# FET_bord.net
KiCad netlist of a schematic drawn in EAGLE
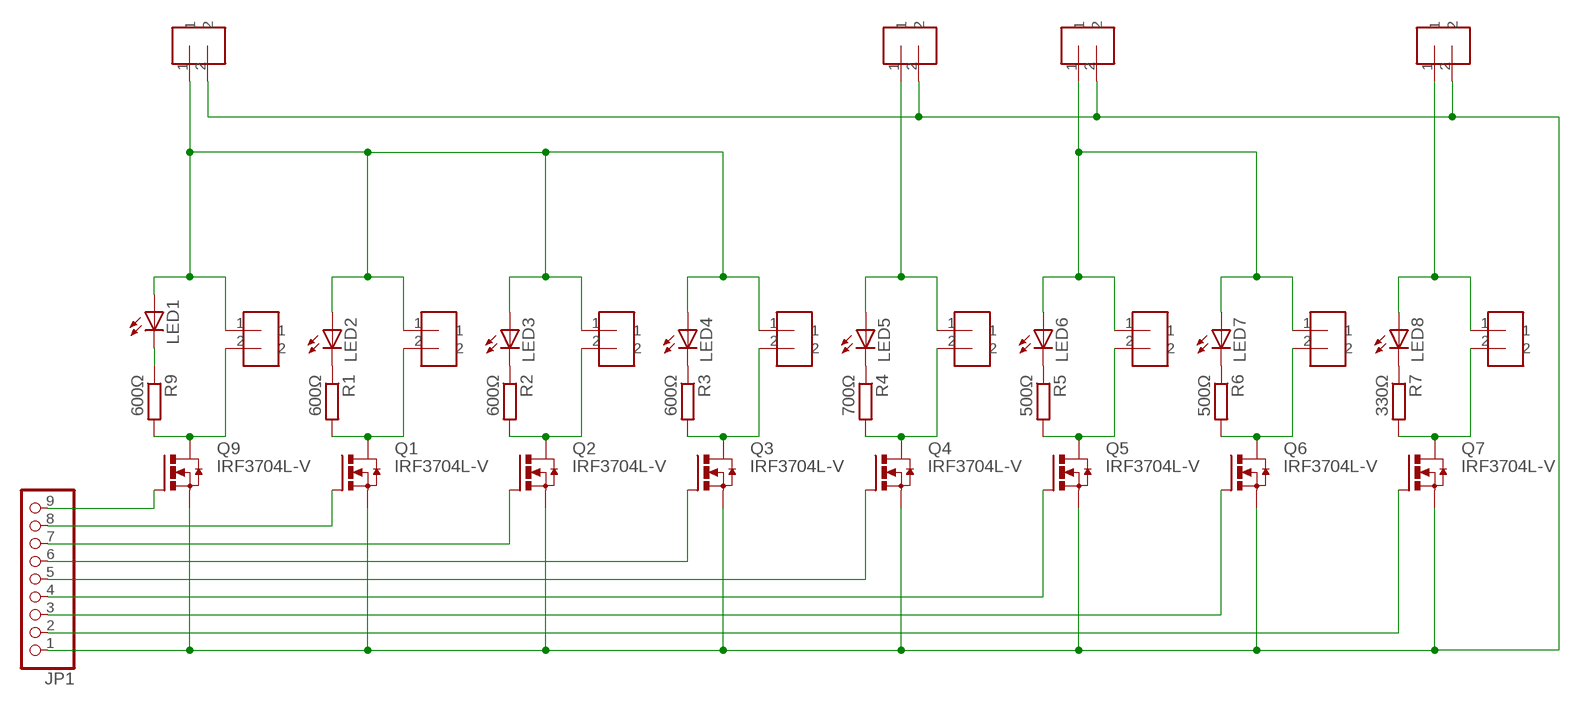
[diagram p0: schematic, sheet 1]

(export (version "E")
  (design (tool "Eeschema 10.0.6"))
  (components
    (comp (ref "3.3V")
      (value "TERMINAL_BLOCK_5.08MM")
      (footprint "eagle-import:TERMINAL_BLOCK_5.8MM")
      (libsource (lib "eagle-import") (part "TERMINAL_BLOCK_5.08MM"))
    )
    (comp (ref "5V")
      (value "TERMINAL_BLOCK_5.08MM")
      (footprint "eagle-import:TERMINAL_BLOCK_5.8MM")
      (libsource (lib "eagle-import") (part "TERMINAL_BLOCK_5.08MM"))
    )
    (comp (ref "7V")
      (value "TERMINAL_BLOCK_5.08MM")
      (footprint "eagle-import:TERMINAL_BLOCK_5.8MM")
      (libsource (lib "eagle-import") (part "TERMINAL_BLOCK_5.08MM"))
    )
    (comp (ref "12V")
      (value "TERMINAL_BLOCK_5.08MM")
      (footprint "eagle-import:TERMINAL_BLOCK_5.8MM")
      (libsource (lib "eagle-import") (part "TERMINAL_BLOCK_5.08MM"))
    )
    (comp (ref "JP1")
      (value "PINHD-1X9")
      (footprint "eagle-import:1X09")
      (libsource (lib "eagle-import") (part "PINHD-1X9"))
    )
    (comp (ref "LED1")
      (value "LED3MM")
      (footprint "eagle-import:LED3MM")
      (libsource (lib "eagle-import") (part "LED3MM"))
    )
    (comp (ref "LED2")
      (value "LED3MM")
      (footprint "eagle-import:LED3MM")
      (libsource (lib "eagle-import") (part "LED3MM"))
    )
    (comp (ref "LED3")
      (value "LED3MM")
      (footprint "eagle-import:LED3MM")
      (libsource (lib "eagle-import") (part "LED3MM"))
    )
    (comp (ref "LED4")
      (value "LED3MM")
      (footprint "eagle-import:LED3MM")
      (libsource (lib "eagle-import") (part "LED3MM"))
    )
    (comp (ref "LED5")
      (value "LED3MM")
      (footprint "eagle-import:LED3MM")
      (libsource (lib "eagle-import") (part "LED3MM"))
    )
    (comp (ref "LED6")
      (value "LED3MM")
      (footprint "eagle-import:LED3MM")
      (libsource (lib "eagle-import") (part "LED3MM"))
    )
    (comp (ref "LED7")
      (value "LED3MM")
      (footprint "eagle-import:LED3MM")
      (libsource (lib "eagle-import") (part "LED3MM"))
    )
    (comp (ref "LED8")
      (value "LED3MM")
      (footprint "eagle-import:LED3MM")
      (libsource (lib "eagle-import") (part "LED3MM"))
    )
    (comp (ref "Q1")
      (value "IRF3704L-V")
      (footprint "eagle-import:TO262-V")
      (libsource (lib "eagle-import") (part "IRF3704L-V"))
    )
    (comp (ref "Q2")
      (value "IRF3704L-V")
      (footprint "eagle-import:TO262-V")
      (libsource (lib "eagle-import") (part "IRF3704L-V"))
    )
    (comp (ref "Q3")
      (value "IRF3704L-V")
      (footprint "eagle-import:TO262-V")
      (libsource (lib "eagle-import") (part "IRF3704L-V"))
    )
    (comp (ref "Q4")
      (value "IRF3704L-V")
      (footprint "eagle-import:TO262-V")
      (libsource (lib "eagle-import") (part "IRF3704L-V"))
    )
    (comp (ref "Q5")
      (value "IRF3704L-V")
      (footprint "eagle-import:TO262-V")
      (libsource (lib "eagle-import") (part "IRF3704L-V"))
    )
    (comp (ref "Q6")
      (value "IRF3704L-V")
      (footprint "eagle-import:TO262-V")
      (libsource (lib "eagle-import") (part "IRF3704L-V"))
    )
    (comp (ref "Q7")
      (value "IRF3704L-V")
      (footprint "eagle-import:TO262-V")
      (libsource (lib "eagle-import") (part "IRF3704L-V"))
    )
    (comp (ref "Q9")
      (value "IRF3704L-V")
      (footprint "eagle-import:TO262-V")
      (libsource (lib "eagle-import") (part "IRF3704L-V"))
    )
    (comp (ref "R1")
      (value "600Ω")
      (footprint "eagle-import:0207_15")
      (libsource (lib "eagle-import") (part "R-EU_0207/15"))
    )
    (comp (ref "R2")
      (value "600Ω")
      (footprint "eagle-import:0207_15")
      (libsource (lib "eagle-import") (part "R-EU_0207/15"))
    )
    (comp (ref "R3")
      (value "600Ω")
      (footprint "eagle-import:0207_15")
      (libsource (lib "eagle-import") (part "R-EU_0207/15"))
    )
    (comp (ref "R4")
      (value "700Ω")
      (footprint "eagle-import:0207_15")
      (libsource (lib "eagle-import") (part "R-EU_0207/15"))
    )
    (comp (ref "R5")
      (value "500Ω")
      (footprint "eagle-import:0207_15")
      (libsource (lib "eagle-import") (part "R-EU_0207/15"))
    )
    (comp (ref "R6")
      (value "500Ω")
      (footprint "eagle-import:0207_15")
      (libsource (lib "eagle-import") (part "R-EU_0207/15"))
    )
    (comp (ref "R7")
      (value "330Ω")
      (footprint "eagle-import:0207_15")
      (libsource (lib "eagle-import") (part "R-EU_0207/15"))
    )
    (comp (ref "R9")
      (value "600Ω")
      (footprint "eagle-import:0207_15")
      (libsource (lib "eagle-import") (part "R-EU_0207/15"))
    )
    (comp (ref "U$1")
      (value "TERMINAL_BLOCK_5.08MM")
      (footprint "eagle-import:TERMINAL_BLOCK_5.8MM")
      (libsource (lib "eagle-import") (part "TERMINAL_BLOCK_5.08MM"))
    )
    (comp (ref "U$2")
      (value "TERMINAL_BLOCK_5.08MM")
      (footprint "eagle-import:TERMINAL_BLOCK_5.8MM")
      (libsource (lib "eagle-import") (part "TERMINAL_BLOCK_5.08MM"))
    )
    (comp (ref "U$3")
      (value "TERMINAL_BLOCK_5.08MM")
      (footprint "eagle-import:TERMINAL_BLOCK_5.8MM")
      (libsource (lib "eagle-import") (part "TERMINAL_BLOCK_5.08MM"))
    )
    (comp (ref "U$4")
      (value "TERMINAL_BLOCK_5.08MM")
      (footprint "eagle-import:TERMINAL_BLOCK_5.8MM")
      (libsource (lib "eagle-import") (part "TERMINAL_BLOCK_5.08MM"))
    )
    (comp (ref "U$5")
      (value "TERMINAL_BLOCK_5.08MM")
      (footprint "eagle-import:TERMINAL_BLOCK_5.8MM")
      (libsource (lib "eagle-import") (part "TERMINAL_BLOCK_5.08MM"))
    )
    (comp (ref "U$6")
      (value "TERMINAL_BLOCK_5.08MM")
      (footprint "eagle-import:TERMINAL_BLOCK_5.8MM")
      (libsource (lib "eagle-import") (part "TERMINAL_BLOCK_5.08MM"))
    )
    (comp (ref "U$7")
      (value "TERMINAL_BLOCK_5.08MM")
      (footprint "eagle-import:TERMINAL_BLOCK_5.8MM")
      (libsource (lib "eagle-import") (part "TERMINAL_BLOCK_5.08MM"))
    )
    (comp (ref "U$8")
      (value "TERMINAL_BLOCK_5.08MM")
      (footprint "eagle-import:TERMINAL_BLOCK_5.8MM")
      (libsource (lib "eagle-import") (part "TERMINAL_BLOCK_5.08MM"))
    )
  )
  (nets
    (net (code "1") (name "Net-(3.3V-Pad1)") (class "Default")
      (node (ref "3.3V") (pin "1") (pinfunction "1_1") (pintype "bidirectional"))
      (node (ref "LED8") (pin "A") (pinfunction "A_A") (pintype "passive"))
      (node (ref "U$8") (pin "1") (pinfunction "1_1") (pintype "bidirectional"))
    )
    (net (code "2") (name "Net-(5V-Pad1)") (class "Default")
      (node (ref "5V") (pin "1") (pinfunction "1_1") (pintype "bidirectional"))
      (node (ref "LED6") (pin "A") (pinfunction "A_A") (pintype "passive"))
      (node (ref "LED7") (pin "A") (pinfunction "A_A") (pintype "passive"))
      (node (ref "U$6") (pin "1") (pinfunction "1_1") (pintype "bidirectional"))
      (node (ref "U$7") (pin "1") (pinfunction "1_1") (pintype "bidirectional"))
    )
    (net (code "3") (name "Net-(7V-Pad1)") (class "Default")
      (node (ref "7V") (pin "1") (pinfunction "1_1") (pintype "bidirectional"))
      (node (ref "LED5") (pin "A") (pinfunction "A_A") (pintype "passive"))
      (node (ref "U$5") (pin "1") (pinfunction "1_1") (pintype "bidirectional"))
    )
    (net (code "4") (name "Net-(12V-Pad1)") (class "Default")
      (node (ref "12V") (pin "1") (pinfunction "1_1") (pintype "bidirectional"))
      (node (ref "LED1") (pin "A") (pinfunction "A_A") (pintype "passive"))
      (node (ref "LED2") (pin "A") (pinfunction "A_A") (pintype "passive"))
      (node (ref "LED3") (pin "A") (pinfunction "A_A") (pintype "passive"))
      (node (ref "LED4") (pin "A") (pinfunction "A_A") (pintype "passive"))
      (node (ref "U$1") (pin "1") (pinfunction "1_1") (pintype "bidirectional"))
      (node (ref "U$2") (pin "1") (pinfunction "1_1") (pintype "bidirectional"))
      (node (ref "U$3") (pin "1") (pinfunction "1_1") (pintype "bidirectional"))
      (node (ref "U$4") (pin "1") (pinfunction "1_1") (pintype "bidirectional"))
    )
    (net (code "5") (name "Net-(LED1-C)") (class "Default")
      (node (ref "LED1") (pin "K") (pinfunction "C_K") (pintype "passive"))
      (node (ref "R9") (pin "1") (pinfunction "1_1") (pintype "passive"))
    )
    (net (code "6") (name "Net-(LED2-C)") (class "Default")
      (node (ref "LED2") (pin "K") (pinfunction "C_K") (pintype "passive"))
      (node (ref "R1") (pin "1") (pinfunction "1_1") (pintype "passive"))
    )
    (net (code "7") (name "Net-(LED3-C)") (class "Default")
      (node (ref "LED3") (pin "K") (pinfunction "C_K") (pintype "passive"))
      (node (ref "R2") (pin "1") (pinfunction "1_1") (pintype "passive"))
    )
    (net (code "8") (name "Net-(LED4-C)") (class "Default")
      (node (ref "LED4") (pin "K") (pinfunction "C_K") (pintype "passive"))
      (node (ref "R3") (pin "1") (pinfunction "1_1") (pintype "passive"))
    )
    (net (code "9") (name "Net-(LED5-C)") (class "Default")
      (node (ref "LED5") (pin "K") (pinfunction "C_K") (pintype "passive"))
      (node (ref "R4") (pin "1") (pinfunction "1_1") (pintype "passive"))
    )
    (net (code "10") (name "Net-(LED6-C)") (class "Default")
      (node (ref "LED6") (pin "K") (pinfunction "C_K") (pintype "passive"))
      (node (ref "R5") (pin "1") (pinfunction "1_1") (pintype "passive"))
    )
    (net (code "11") (name "Net-(LED7-C)") (class "Default")
      (node (ref "LED7") (pin "K") (pinfunction "C_K") (pintype "passive"))
      (node (ref "R6") (pin "1") (pinfunction "1_1") (pintype "passive"))
    )
    (net (code "12") (name "Net-(LED8-C)") (class "Default")
      (node (ref "LED8") (pin "K") (pinfunction "C_K") (pintype "passive"))
      (node (ref "R7") (pin "1") (pinfunction "1_1") (pintype "passive"))
    )
    (net (code "13") (name "Net-(Q1-D)") (class "Default")
      (node (ref "Q1") (pin "2") (pinfunction "D_2") (pintype "passive"))
      (node (ref "R1") (pin "2") (pinfunction "2_2") (pintype "passive"))
      (node (ref "U$2") (pin "2") (pinfunction "2_2") (pintype "bidirectional"))
    )
    (net (code "14") (name "Net-(Q1-G)") (class "Default")
      (node (ref "JP1") (pin "8") (pinfunction "8_8") (pintype "passive"))
      (node (ref "Q1") (pin "1") (pinfunction "G_1") (pintype "passive"))
    )
    (net (code "15") (name "Net-(Q1-S)") (class "Default")
      (node (ref "12V") (pin "2") (pinfunction "2_2") (pintype "bidirectional"))
      (node (ref "3.3V") (pin "2") (pinfunction "2_2") (pintype "bidirectional"))
      (node (ref "5V") (pin "2") (pinfunction "2_2") (pintype "bidirectional"))
      (node (ref "7V") (pin "2") (pinfunction "2_2") (pintype "bidirectional"))
      (node (ref "JP1") (pin "1") (pinfunction "1_1") (pintype "passive"))
      (node (ref "Q1") (pin "3") (pinfunction "S_3") (pintype "passive"))
      (node (ref "Q2") (pin "3") (pinfunction "S_3") (pintype "passive"))
      (node (ref "Q3") (pin "3") (pinfunction "S_3") (pintype "passive"))
      (node (ref "Q4") (pin "3") (pinfunction "S_3") (pintype "passive"))
      (node (ref "Q5") (pin "3") (pinfunction "S_3") (pintype "passive"))
      (node (ref "Q6") (pin "3") (pinfunction "S_3") (pintype "passive"))
      (node (ref "Q7") (pin "3") (pinfunction "S_3") (pintype "passive"))
      (node (ref "Q9") (pin "3") (pinfunction "S_3") (pintype "passive"))
    )
    (net (code "16") (name "Net-(Q2-D)") (class "Default")
      (node (ref "Q2") (pin "2") (pinfunction "D_2") (pintype "passive"))
      (node (ref "R2") (pin "2") (pinfunction "2_2") (pintype "passive"))
      (node (ref "U$3") (pin "2") (pinfunction "2_2") (pintype "bidirectional"))
    )
    (net (code "17") (name "Net-(Q2-G)") (class "Default")
      (node (ref "JP1") (pin "7") (pinfunction "7_7") (pintype "passive"))
      (node (ref "Q2") (pin "1") (pinfunction "G_1") (pintype "passive"))
    )
    (net (code "18") (name "Net-(Q3-D)") (class "Default")
      (node (ref "Q3") (pin "2") (pinfunction "D_2") (pintype "passive"))
      (node (ref "R3") (pin "2") (pinfunction "2_2") (pintype "passive"))
      (node (ref "U$4") (pin "2") (pinfunction "2_2") (pintype "bidirectional"))
    )
    (net (code "19") (name "Net-(Q3-G)") (class "Default")
      (node (ref "JP1") (pin "6") (pinfunction "6_6") (pintype "passive"))
      (node (ref "Q3") (pin "1") (pinfunction "G_1") (pintype "passive"))
    )
    (net (code "20") (name "Net-(Q4-D)") (class "Default")
      (node (ref "Q4") (pin "2") (pinfunction "D_2") (pintype "passive"))
      (node (ref "R4") (pin "2") (pinfunction "2_2") (pintype "passive"))
      (node (ref "U$5") (pin "2") (pinfunction "2_2") (pintype "bidirectional"))
    )
    (net (code "21") (name "Net-(Q4-G)") (class "Default")
      (node (ref "JP1") (pin "5") (pinfunction "5_5") (pintype "passive"))
      (node (ref "Q4") (pin "1") (pinfunction "G_1") (pintype "passive"))
    )
    (net (code "22") (name "Net-(Q5-D)") (class "Default")
      (node (ref "Q5") (pin "2") (pinfunction "D_2") (pintype "passive"))
      (node (ref "R5") (pin "2") (pinfunction "2_2") (pintype "passive"))
      (node (ref "U$6") (pin "2") (pinfunction "2_2") (pintype "bidirectional"))
    )
    (net (code "23") (name "Net-(Q5-G)") (class "Default")
      (node (ref "JP1") (pin "4") (pinfunction "4_4") (pintype "passive"))
      (node (ref "Q5") (pin "1") (pinfunction "G_1") (pintype "passive"))
    )
    (net (code "24") (name "Net-(Q6-D)") (class "Default")
      (node (ref "Q6") (pin "2") (pinfunction "D_2") (pintype "passive"))
      (node (ref "R6") (pin "2") (pinfunction "2_2") (pintype "passive"))
      (node (ref "U$7") (pin "2") (pinfunction "2_2") (pintype "bidirectional"))
    )
    (net (code "25") (name "Net-(Q6-G)") (class "Default")
      (node (ref "JP1") (pin "3") (pinfunction "3_3") (pintype "passive"))
      (node (ref "Q6") (pin "1") (pinfunction "G_1") (pintype "passive"))
    )
    (net (code "26") (name "Net-(Q7-D)") (class "Default")
      (node (ref "Q7") (pin "2") (pinfunction "D_2") (pintype "passive"))
      (node (ref "R7") (pin "2") (pinfunction "2_2") (pintype "passive"))
      (node (ref "U$8") (pin "2") (pinfunction "2_2") (pintype "bidirectional"))
    )
    (net (code "27") (name "Net-(Q7-G)") (class "Default")
      (node (ref "JP1") (pin "2") (pinfunction "2_2") (pintype "passive"))
      (node (ref "Q7") (pin "1") (pinfunction "G_1") (pintype "passive"))
    )
    (net (code "28") (name "Net-(Q9-D)") (class "Default")
      (node (ref "Q9") (pin "2") (pinfunction "D_2") (pintype "passive"))
      (node (ref "R9") (pin "2") (pinfunction "2_2") (pintype "passive"))
      (node (ref "U$1") (pin "2") (pinfunction "2_2") (pintype "bidirectional"))
    )
    (net (code "29") (name "Net-(Q9-G)") (class "Default")
      (node (ref "JP1") (pin "9") (pinfunction "9_9") (pintype "passive"))
      (node (ref "Q9") (pin "1") (pinfunction "G_1") (pintype "passive"))
    )
  )
)
